# led_board.net
KiCad netlist of a schematic drawn in EAGLE
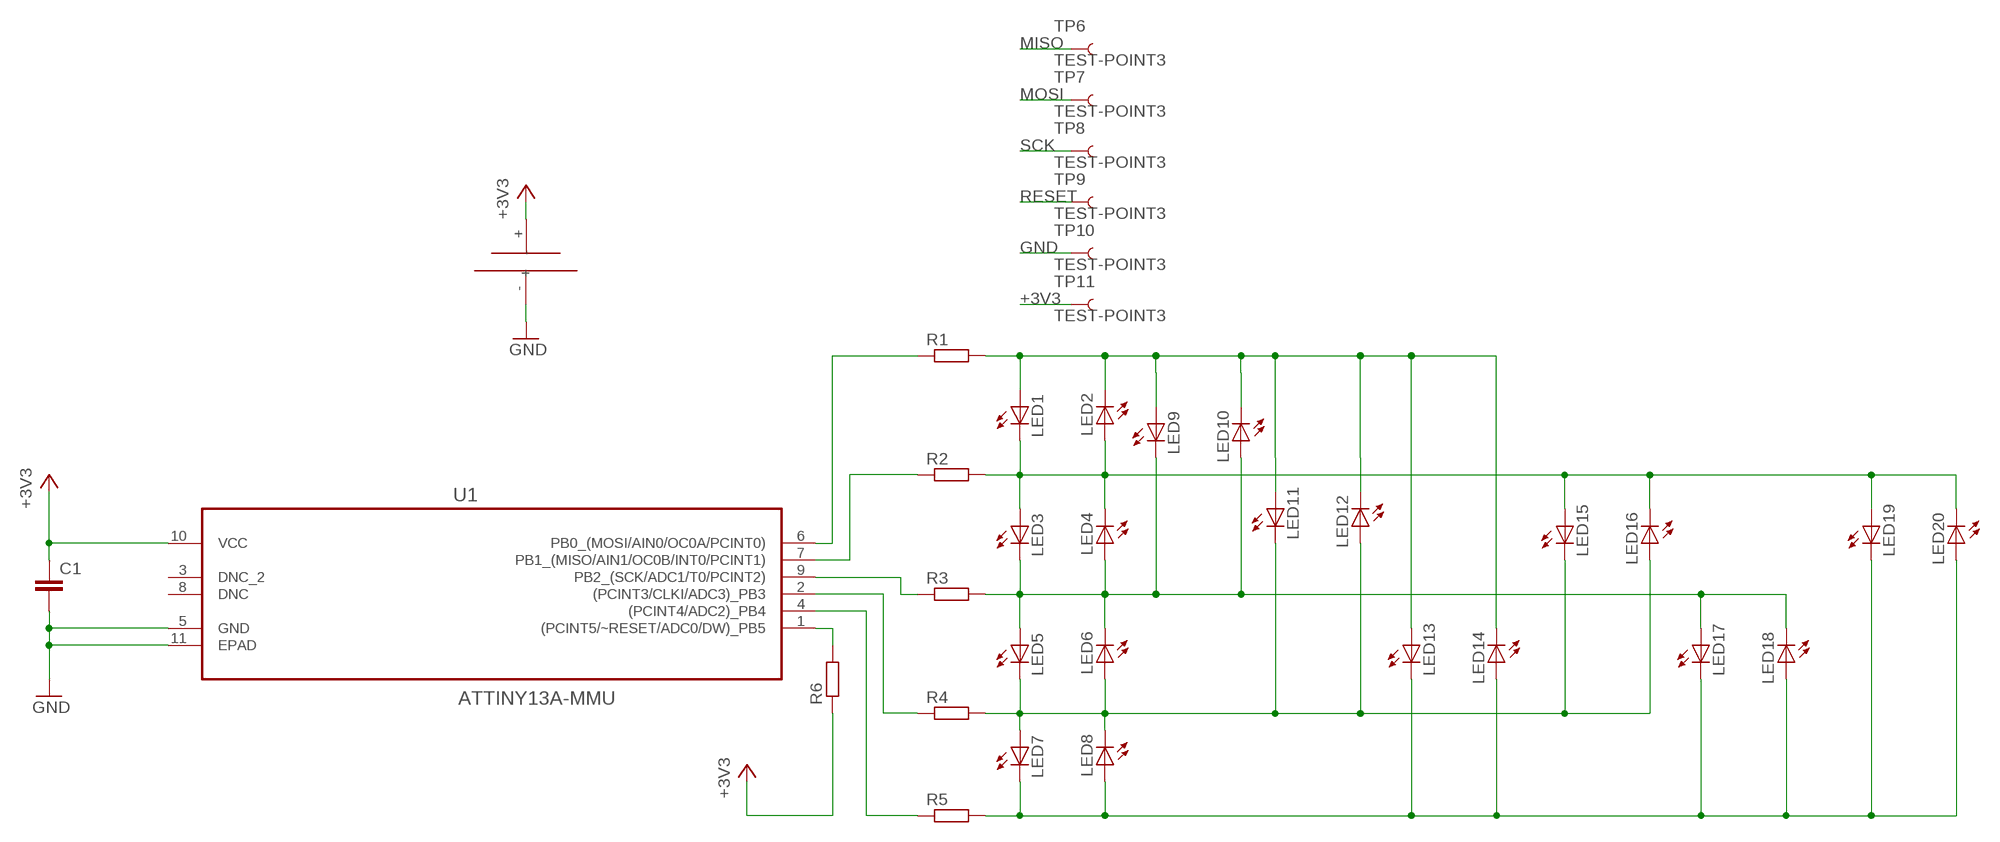
[diagram p0: schematic, sheet 1]

(export (version "E")
  (design (tool "Eeschema 10.0.6"))
  (components
    (comp (ref "C1")
      (value "C-EUC0603")
      (footprint "eagle-import:C0603")
      (libsource (lib "eagle-import") (part "C-EUC0603"))
    )
    (comp (ref "LED1")
      (value "LED0603")
      (footprint "eagle-import:LED-0603")
      (libsource (lib "eagle-import") (part "LED0603"))
    )
    (comp (ref "LED2")
      (value "LED0603")
      (footprint "eagle-import:LED-0603")
      (libsource (lib "eagle-import") (part "LED0603"))
    )
    (comp (ref "LED3")
      (value "LED0603")
      (footprint "eagle-import:LED-0603")
      (libsource (lib "eagle-import") (part "LED0603"))
    )
    (comp (ref "LED4")
      (value "LED0603")
      (footprint "eagle-import:LED-0603")
      (libsource (lib "eagle-import") (part "LED0603"))
    )
    (comp (ref "LED5")
      (value "LED0603")
      (footprint "eagle-import:LED-0603")
      (libsource (lib "eagle-import") (part "LED0603"))
    )
    (comp (ref "LED6")
      (value "LED0603")
      (footprint "eagle-import:LED-0603")
      (libsource (lib "eagle-import") (part "LED0603"))
    )
    (comp (ref "LED7")
      (value "LED0603")
      (footprint "eagle-import:LED-0603")
      (libsource (lib "eagle-import") (part "LED0603"))
    )
    (comp (ref "LED8")
      (value "LED0603")
      (footprint "eagle-import:LED-0603")
      (libsource (lib "eagle-import") (part "LED0603"))
    )
    (comp (ref "LED9")
      (value "LED0603")
      (footprint "eagle-import:LED-0603")
      (libsource (lib "eagle-import") (part "LED0603"))
    )
    (comp (ref "LED10")
      (value "LED0603")
      (footprint "eagle-import:LED-0603")
      (libsource (lib "eagle-import") (part "LED0603"))
    )
    (comp (ref "LED11")
      (value "LED0603")
      (footprint "eagle-import:LED-0603")
      (libsource (lib "eagle-import") (part "LED0603"))
    )
    (comp (ref "LED12")
      (value "LED0603")
      (footprint "eagle-import:LED-0603")
      (libsource (lib "eagle-import") (part "LED0603"))
    )
    (comp (ref "LED13")
      (value "LED0603")
      (footprint "eagle-import:LED-0603")
      (libsource (lib "eagle-import") (part "LED0603"))
    )
    (comp (ref "LED14")
      (value "LED0603")
      (footprint "eagle-import:LED-0603")
      (libsource (lib "eagle-import") (part "LED0603"))
    )
    (comp (ref "LED15")
      (value "LED0603")
      (footprint "eagle-import:LED-0603")
      (libsource (lib "eagle-import") (part "LED0603"))
    )
    (comp (ref "LED16")
      (value "LED0603")
      (footprint "eagle-import:LED-0603")
      (libsource (lib "eagle-import") (part "LED0603"))
    )
    (comp (ref "LED17")
      (value "LED0603")
      (footprint "eagle-import:LED-0603")
      (libsource (lib "eagle-import") (part "LED0603"))
    )
    (comp (ref "LED18")
      (value "LED0603")
      (footprint "eagle-import:LED-0603")
      (libsource (lib "eagle-import") (part "LED0603"))
    )
    (comp (ref "LED19")
      (value "LED0603")
      (footprint "eagle-import:LED-0603")
      (libsource (lib "eagle-import") (part "LED0603"))
    )
    (comp (ref "LED20")
      (value "LED0603")
      (footprint "eagle-import:LED-0603")
      (libsource (lib "eagle-import") (part "LED0603"))
    )
    (comp (ref "R1")
      (value "R-EU_R0603")
      (footprint "eagle-import:R0603")
      (libsource (lib "eagle-import") (part "R-EU_R0603"))
    )
    (comp (ref "R2")
      (value "R-EU_R0603")
      (footprint "eagle-import:R0603")
      (libsource (lib "eagle-import") (part "R-EU_R0603"))
    )
    (comp (ref "R3")
      (value "R-EU_R0603")
      (footprint "eagle-import:R0603")
      (libsource (lib "eagle-import") (part "R-EU_R0603"))
    )
    (comp (ref "R4")
      (value "R-EU_R0603")
      (footprint "eagle-import:R0603")
      (libsource (lib "eagle-import") (part "R-EU_R0603"))
    )
    (comp (ref "R5")
      (value "R-EU_R0603")
      (footprint "eagle-import:R0603")
      (libsource (lib "eagle-import") (part "R-EU_R0603"))
    )
    (comp (ref "R6")
      (value "R-EU_R0603")
      (footprint "eagle-import:R0603")
      (libsource (lib "eagle-import") (part "R-EU_R0603"))
    )
    (comp (ref "TP6")
      (value "TEST-POINT3")
      (footprint "eagle-import:PAD.03X.03")
      (libsource (lib "eagle-import") (part "TEST-POINT3"))
    )
    (comp (ref "TP7")
      (value "TEST-POINT3")
      (footprint "eagle-import:PAD.03X.03")
      (libsource (lib "eagle-import") (part "TEST-POINT3"))
    )
    (comp (ref "TP8")
      (value "TEST-POINT3")
      (footprint "eagle-import:PAD.03X.03")
      (libsource (lib "eagle-import") (part "TEST-POINT3"))
    )
    (comp (ref "TP9")
      (value "TEST-POINT3")
      (footprint "eagle-import:PAD.03X.03")
      (libsource (lib "eagle-import") (part "TEST-POINT3"))
    )
    (comp (ref "TP10")
      (value "TEST-POINT3")
      (footprint "eagle-import:PAD.03X.03")
      (libsource (lib "eagle-import") (part "TEST-POINT3"))
    )
    (comp (ref "TP11")
      (value "TEST-POINT3")
      (footprint "eagle-import:PAD.03X.03")
      (libsource (lib "eagle-import") (part "TEST-POINT3"))
    )
    (comp (ref "U$1")
      (value "BH500")
      (footprint "eagle-import:BAT1220_BH500")
      (libsource (lib "eagle-import") (part "BH500"))
    )
    (comp (ref "U1")
      (value "ATTINY13A-MMU")
      (footprint "eagle-import:DFN300X300X100-11N")
      (libsource (lib "eagle-import") (part "ATTINY13A-MMU"))
    )
  )
  (nets
    (net (code "1") (name "+3V3") (class "Default")
      (node (ref "C1") (pin "1") (pinfunction "1_1") (pintype "passive"))
      (node (ref "R6") (pin "1") (pinfunction "1_1") (pintype "passive"))
      (node (ref "TP11") (pin "P$1") (pinfunction "1_P$1") (pintype "bidirectional"))
      (node (ref "U$1") (pin "+") (pinfunction "+_+") (pintype "passive"))
      (node (ref "U1") (pin "10") (pinfunction "VCC_10") (pintype "power_in"))
    )
    (net (code "2") (name "/MISO") (class "Default")
      (node (ref "R2") (pin "1") (pinfunction "1_1") (pintype "passive"))
      (node (ref "TP6") (pin "P$1") (pinfunction "1_P$1") (pintype "bidirectional"))
      (node (ref "U1") (pin "7") (pinfunction "PB1_(MISO/AIN1/OC0B/INT0/PCINT1)_7") (pintype "bidirectional"))
    )
    (net (code "3") (name "/MOSI") (class "Default")
      (node (ref "R1") (pin "1") (pinfunction "1_1") (pintype "passive"))
      (node (ref "TP7") (pin "P$1") (pinfunction "1_P$1") (pintype "bidirectional"))
      (node (ref "U1") (pin "6") (pinfunction "PB0_(MOSI/AIN0/OC0A/PCINT0)_6") (pintype "bidirectional"))
    )
    (net (code "4") (name "/RESET") (class "Default")
      (node (ref "R6") (pin "2") (pinfunction "2_2") (pintype "passive"))
      (node (ref "TP9") (pin "P$1") (pinfunction "1_P$1") (pintype "bidirectional"))
      (node (ref "U1") (pin "1") (pinfunction "(PCINT5/~{RESET/ADC0/DW})_PB5_1") (pintype "bidirectional"))
    )
    (net (code "5") (name "/SCK") (class "Default")
      (node (ref "R3") (pin "1") (pinfunction "1_1") (pintype "passive"))
      (node (ref "TP8") (pin "P$1") (pinfunction "1_P$1") (pintype "bidirectional"))
      (node (ref "U1") (pin "9") (pinfunction "PB2_(SCK/ADC1/T0/PCINT2)_9") (pintype "bidirectional"))
    )
    (net (code "6") (name "GND") (class "Default")
      (node (ref "C1") (pin "2") (pinfunction "2_2") (pintype "passive"))
      (node (ref "TP10") (pin "P$1") (pinfunction "1_P$1") (pintype "bidirectional"))
      (node (ref "U$1") (pin "-") (pinfunction "-_-") (pintype "passive"))
      (node (ref "U1") (pin "11") (pinfunction "EPAD_11") (pintype "passive"))
      (node (ref "U1") (pin "5") (pinfunction "GND_5") (pintype "passive"))
    )
    (net (code "7") (name "Net-(LED1-PadA)") (class "Default")
      (node (ref "LED1") (pin "A") (pinfunction "A_A") (pintype "passive"))
      (node (ref "LED10") (pin "C") (pinfunction "C_C") (pintype "passive"))
      (node (ref "LED11") (pin "A") (pinfunction "A_A") (pintype "passive"))
      (node (ref "LED12") (pin "C") (pinfunction "C_C") (pintype "passive"))
      (node (ref "LED13") (pin "A") (pinfunction "A_A") (pintype "passive"))
      (node (ref "LED14") (pin "C") (pinfunction "C_C") (pintype "passive"))
      (node (ref "LED2") (pin "C") (pinfunction "C_C") (pintype "passive"))
      (node (ref "LED9") (pin "A") (pinfunction "A_A") (pintype "passive"))
      (node (ref "R1") (pin "2") (pinfunction "2_2") (pintype "passive"))
    )
    (net (code "8") (name "Net-(LED1-PadC)") (class "Default")
      (node (ref "LED1") (pin "C") (pinfunction "C_C") (pintype "passive"))
      (node (ref "LED15") (pin "A") (pinfunction "A_A") (pintype "passive"))
      (node (ref "LED16") (pin "C") (pinfunction "C_C") (pintype "passive"))
      (node (ref "LED19") (pin "A") (pinfunction "A_A") (pintype "passive"))
      (node (ref "LED2") (pin "A") (pinfunction "A_A") (pintype "passive"))
      (node (ref "LED20") (pin "C") (pinfunction "C_C") (pintype "passive"))
      (node (ref "LED3") (pin "A") (pinfunction "A_A") (pintype "passive"))
      (node (ref "LED4") (pin "C") (pinfunction "C_C") (pintype "passive"))
      (node (ref "R2") (pin "2") (pinfunction "2_2") (pintype "passive"))
    )
    (net (code "9") (name "Net-(LED10-PadA)") (class "Default")
      (node (ref "LED10") (pin "A") (pinfunction "A_A") (pintype "passive"))
      (node (ref "LED17") (pin "A") (pinfunction "A_A") (pintype "passive"))
      (node (ref "LED18") (pin "C") (pinfunction "C_C") (pintype "passive"))
      (node (ref "LED3") (pin "C") (pinfunction "C_C") (pintype "passive"))
      (node (ref "LED4") (pin "A") (pinfunction "A_A") (pintype "passive"))
      (node (ref "LED5") (pin "A") (pinfunction "A_A") (pintype "passive"))
      (node (ref "LED6") (pin "C") (pinfunction "C_C") (pintype "passive"))
      (node (ref "LED9") (pin "C") (pinfunction "C_C") (pintype "passive"))
      (node (ref "R3") (pin "2") (pinfunction "2_2") (pintype "passive"))
    )
    (net (code "10") (name "Net-(LED11-PadC)") (class "Default")
      (node (ref "LED11") (pin "C") (pinfunction "C_C") (pintype "passive"))
      (node (ref "LED12") (pin "A") (pinfunction "A_A") (pintype "passive"))
      (node (ref "LED15") (pin "C") (pinfunction "C_C") (pintype "passive"))
      (node (ref "LED16") (pin "A") (pinfunction "A_A") (pintype "passive"))
      (node (ref "LED5") (pin "C") (pinfunction "C_C") (pintype "passive"))
      (node (ref "LED6") (pin "A") (pinfunction "A_A") (pintype "passive"))
      (node (ref "LED7") (pin "A") (pinfunction "A_A") (pintype "passive"))
      (node (ref "LED8") (pin "C") (pinfunction "C_C") (pintype "passive"))
      (node (ref "R4") (pin "2") (pinfunction "2_2") (pintype "passive"))
    )
    (net (code "11") (name "Net-(LED13-PadC)") (class "Default")
      (node (ref "LED13") (pin "C") (pinfunction "C_C") (pintype "passive"))
      (node (ref "LED14") (pin "A") (pinfunction "A_A") (pintype "passive"))
      (node (ref "LED17") (pin "C") (pinfunction "C_C") (pintype "passive"))
      (node (ref "LED18") (pin "A") (pinfunction "A_A") (pintype "passive"))
      (node (ref "LED19") (pin "C") (pinfunction "C_C") (pintype "passive"))
      (node (ref "LED20") (pin "A") (pinfunction "A_A") (pintype "passive"))
      (node (ref "LED7") (pin "C") (pinfunction "C_C") (pintype "passive"))
      (node (ref "LED8") (pin "A") (pinfunction "A_A") (pintype "passive"))
      (node (ref "R5") (pin "2") (pinfunction "2_2") (pintype "passive"))
    )
    (net (code "12") (name "Net-(U1-(PCINT3{slash}CLKI{slash}ADC3)_PB3)") (class "Default")
      (node (ref "R4") (pin "1") (pinfunction "1_1") (pintype "passive"))
      (node (ref "U1") (pin "2") (pinfunction "(PCINT3/CLKI/ADC3)_PB3_2") (pintype "bidirectional"))
    )
    (net (code "13") (name "Net-(U1-(PCINT4{slash}ADC2)_PB4)") (class "Default")
      (node (ref "R5") (pin "1") (pinfunction "1_1") (pintype "passive"))
      (node (ref "U1") (pin "4") (pinfunction "(PCINT4/ADC2)_PB4_4") (pintype "bidirectional"))
    )
    (net (code "14") (name "unconnected-(U1-DNC-Pad8)") (class "Default")
      (node (ref "U1") (pin "8") (pinfunction "DNC_8") (pintype "no_connect"))
    )
    (net (code "15") (name "unconnected-(U1-DNC_2-Pad3)") (class "Default")
      (node (ref "U1") (pin "3") (pinfunction "DNC_2_3") (pintype "no_connect"))
    )
  )
)
